# FLOM_Converter.net
KiCad netlist of a schematic drawn in Altium Designer
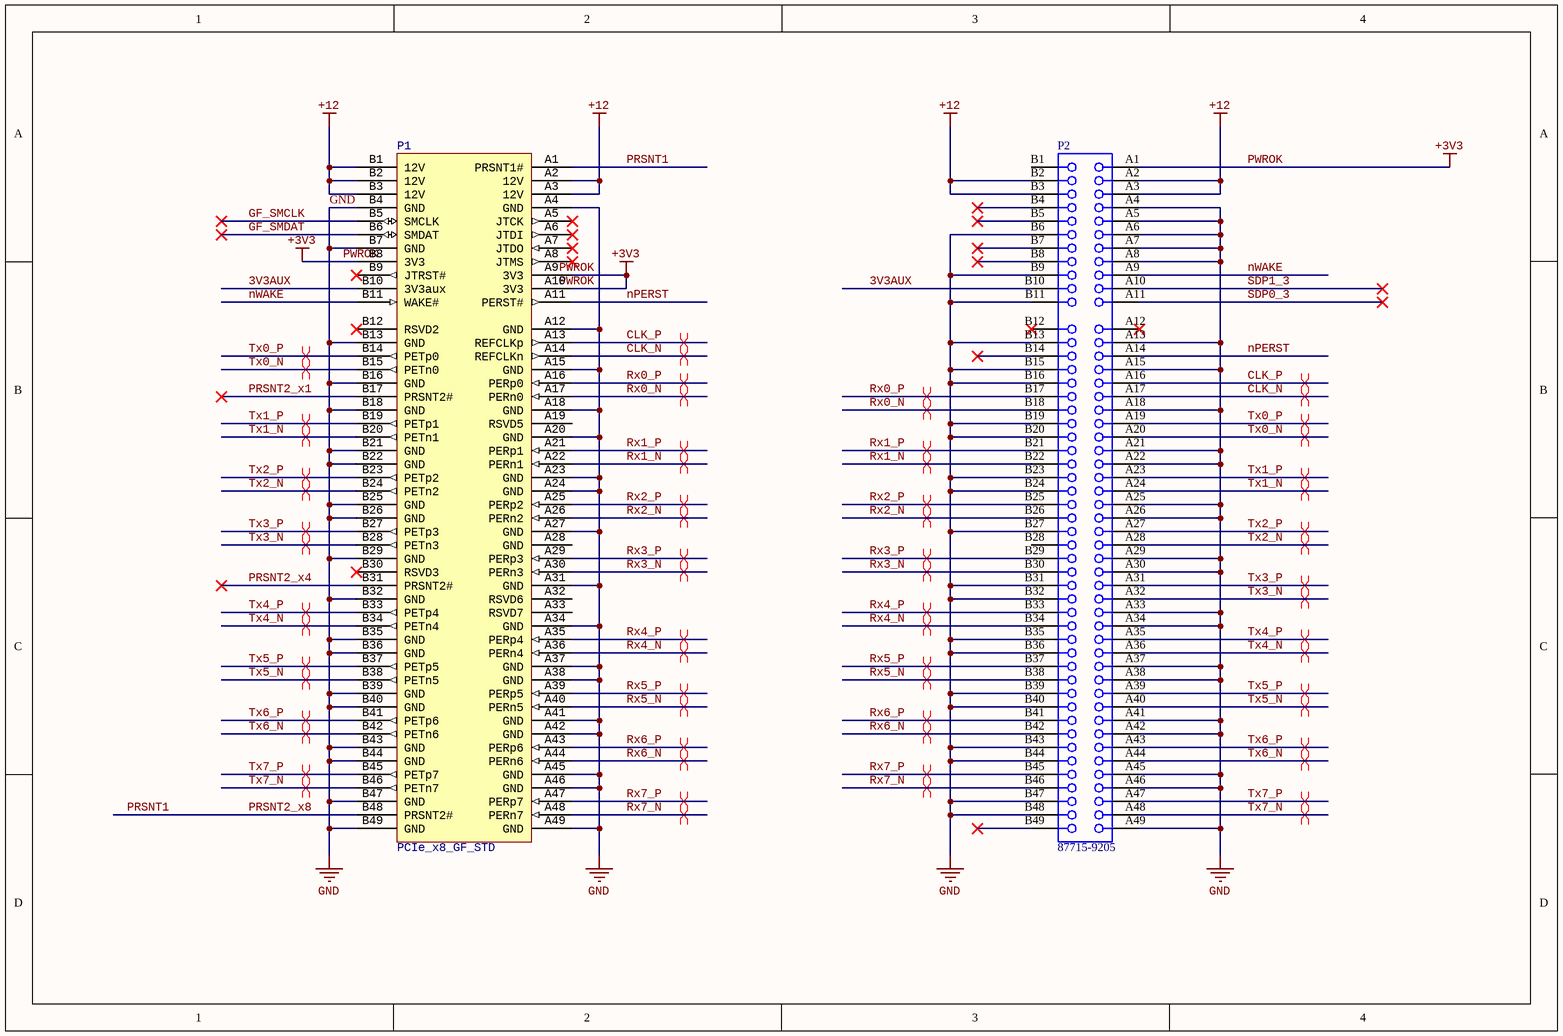
[diagram p0: FLOM_Converter.SchDoc]

(export (version "E")
  (design (tool "Eeschema 10.0.6"))
  (components
    (comp (ref "P1")
      (value "PCIe_x8_GF_STD")
      (footprint "PCIe_x8_GF_STD")
      (libsource (lib "FLOM_Converter") (part "PCIe_x8_GF_STD"))
    )
    (comp (ref "P2")
      (value "87715-9205")
      (footprint "BTB1-00-2V98")
      (description "Board-to-Board Connector, PTH, Vertical, Pitch 1.00mm, 98-Position")
      (fields (field (name "PUBLISHER") "Altium"))
      (libsource (lib "FLOM_Converter") (part "CMP-0001-00128-1"))
    )
  )
  (nets
    (net (code "1") (name "+3V3") (class "Default")
      (node (ref "P1") (pin "A10") (pinfunction "3V3_A10") (pintype "power_in"))
      (node (ref "P1") (pin "A9") (pinfunction "3V3_A9") (pintype "power_in"))
      (node (ref "P1") (pin "B8") (pinfunction "3V3_B8") (pintype "power_in"))
      (node (ref "P2") (pin "A1") (pinfunction "A1_A1") (pintype "passive"))
    )
    (net (code "2") (name "+12") (class "Default")
      (node (ref "P1") (pin "A2") (pinfunction "12V_A2") (pintype "power_in"))
      (node (ref "P1") (pin "A3") (pinfunction "12V_A3") (pintype "power_in"))
      (node (ref "P1") (pin "B1") (pinfunction "12V_B1") (pintype "power_in"))
      (node (ref "P1") (pin "B2") (pinfunction "12V_B2") (pintype "power_in"))
      (node (ref "P1") (pin "B3") (pinfunction "12V_B3") (pintype "power_in"))
      (node (ref "P2") (pin "A2") (pinfunction "A2_A2") (pintype "passive"))
      (node (ref "P2") (pin "A3") (pinfunction "A3_A3") (pintype "passive"))
      (node (ref "P2") (pin "B2") (pinfunction "B2_B2") (pintype "passive"))
      (node (ref "P2") (pin "B3") (pinfunction "B3_B3") (pintype "passive"))
    )
    (net (code "3") (name "/3V3AUX") (class "Default")
      (node (ref "P1") (pin "B10") (pinfunction "3V3aux_B10") (pintype "power_in"))
      (node (ref "P2") (pin "B10") (pinfunction "B10_B10") (pintype "passive"))
    )
    (net (code "5") (name "/CLK_N") (class "Default")
      (node (ref "P1") (pin "A14") (pinfunction "REFCLKn_A14") (pintype "output"))
      (node (ref "P2") (pin "A17") (pinfunction "A17_A17") (pintype "passive"))
    )
    (net (code "6") (name "/CLK_P") (class "Default")
      (node (ref "P1") (pin "A13") (pinfunction "REFCLKp_A13") (pintype "output"))
      (node (ref "P2") (pin "A16") (pinfunction "A16_A16") (pintype "passive"))
    )
    (net (code "7") (name "/GF_SMCLK") (class "Default")
      (node (ref "P1") (pin "B5") (pinfunction "SMCLK_B5") (pintype "bidirectional+no_connect"))
    )
    (net (code "8") (name "/GF_SMDAT") (class "Default")
      (node (ref "P1") (pin "B6") (pinfunction "SMDAT_B6") (pintype "bidirectional+no_connect"))
    )
    (net (code "9") (name "/PRSNT1") (class "Default")
      (node (ref "P1") (pin "A1") (pinfunction "PRSNT1#_A1") (pintype "passive"))
      (node (ref "P1") (pin "B48") (pinfunction "PRSNT2#_B48") (pintype "passive"))
    )
    (net (code "10") (name "/PRSNT2_x1") (class "Default")
      (node (ref "P1") (pin "B17") (pinfunction "PRSNT2#_B17") (pintype "passive+no_connect"))
    )
    (net (code "11") (name "/PRSNT2_x4") (class "Default")
      (node (ref "P1") (pin "B31") (pinfunction "PRSNT2#_B31") (pintype "passive+no_connect"))
    )
    (net (code "12") (name "/Rx0_N") (class "Default")
      (node (ref "P1") (pin "A17") (pinfunction "PERn0_A17") (pintype "input"))
      (node (ref "P2") (pin "B18") (pinfunction "B18_B18") (pintype "passive"))
    )
    (net (code "13") (name "/Rx0_P") (class "Default")
      (node (ref "P1") (pin "A16") (pinfunction "PERp0_A16") (pintype "input"))
      (node (ref "P2") (pin "B17") (pinfunction "B17_B17") (pintype "passive"))
    )
    (net (code "14") (name "/Rx1_N") (class "Default")
      (node (ref "P1") (pin "A22") (pinfunction "PERn1_A22") (pintype "input"))
      (node (ref "P2") (pin "B22") (pinfunction "B22_B22") (pintype "passive"))
    )
    (net (code "15") (name "/Rx1_P") (class "Default")
      (node (ref "P1") (pin "A21") (pinfunction "PERp1_A21") (pintype "input"))
      (node (ref "P2") (pin "B21") (pinfunction "B21_B21") (pintype "passive"))
    )
    (net (code "16") (name "/Rx2_N") (class "Default")
      (node (ref "P1") (pin "A26") (pinfunction "PERn2_A26") (pintype "input"))
      (node (ref "P2") (pin "B26") (pinfunction "B26_B26") (pintype "passive"))
    )
    (net (code "17") (name "/Rx2_P") (class "Default")
      (node (ref "P1") (pin "A25") (pinfunction "PERp2_A25") (pintype "input"))
      (node (ref "P2") (pin "B25") (pinfunction "B25_B25") (pintype "passive"))
    )
    (net (code "18") (name "/Rx3_N") (class "Default")
      (node (ref "P1") (pin "A30") (pinfunction "PERn3_A30") (pintype "input"))
      (node (ref "P2") (pin "B30") (pinfunction "B30_B30") (pintype "passive"))
    )
    (net (code "19") (name "/Rx3_P") (class "Default")
      (node (ref "P1") (pin "A29") (pinfunction "PERp3_A29") (pintype "input"))
      (node (ref "P2") (pin "B29") (pinfunction "B29_B29") (pintype "passive"))
    )
    (net (code "20") (name "/Rx4_N") (class "Default")
      (node (ref "P1") (pin "A36") (pinfunction "PERn4_A36") (pintype "input"))
      (node (ref "P2") (pin "B34") (pinfunction "B34_B34") (pintype "passive"))
    )
    (net (code "21") (name "/Rx4_P") (class "Default")
      (node (ref "P1") (pin "A35") (pinfunction "PERp4_A35") (pintype "input"))
      (node (ref "P2") (pin "B33") (pinfunction "B33_B33") (pintype "passive"))
    )
    (net (code "22") (name "/Rx5_N") (class "Default")
      (node (ref "P1") (pin "A40") (pinfunction "PERn5_A40") (pintype "input"))
      (node (ref "P2") (pin "B38") (pinfunction "B38_B38") (pintype "passive"))
    )
    (net (code "23") (name "/Rx5_P") (class "Default")
      (node (ref "P1") (pin "A39") (pinfunction "PERp5_A39") (pintype "input"))
      (node (ref "P2") (pin "B37") (pinfunction "B37_B37") (pintype "passive"))
    )
    (net (code "24") (name "/Rx6_N") (class "Default")
      (node (ref "P1") (pin "A44") (pinfunction "PERn6_A44") (pintype "input"))
      (node (ref "P2") (pin "B42") (pinfunction "B42_B42") (pintype "passive"))
    )
    (net (code "25") (name "/Rx6_P") (class "Default")
      (node (ref "P1") (pin "A43") (pinfunction "PERp6_A43") (pintype "input"))
      (node (ref "P2") (pin "B41") (pinfunction "B41_B41") (pintype "passive"))
    )
    (net (code "26") (name "/Rx7_N") (class "Default")
      (node (ref "P1") (pin "A48") (pinfunction "PERn7_A48") (pintype "input"))
      (node (ref "P2") (pin "B46") (pinfunction "B46_B46") (pintype "passive"))
    )
    (net (code "27") (name "/Rx7_P") (class "Default")
      (node (ref "P1") (pin "A47") (pinfunction "PERp7_A47") (pintype "input"))
      (node (ref "P2") (pin "B45") (pinfunction "B45_B45") (pintype "passive"))
    )
    (net (code "28") (name "/SDP0_3") (class "Default")
      (node (ref "P2") (pin "A11") (pinfunction "A11_A11") (pintype "passive+no_connect"))
    )
    (net (code "29") (name "/SDP1_3") (class "Default")
      (node (ref "P2") (pin "A10") (pinfunction "A10_A10") (pintype "passive+no_connect"))
    )
    (net (code "30") (name "/Tx0_N") (class "Default")
      (node (ref "P1") (pin "B15") (pinfunction "PETn0_B15") (pintype "output"))
      (node (ref "P2") (pin "A20") (pinfunction "A20_A20") (pintype "passive"))
    )
    (net (code "31") (name "/Tx0_P") (class "Default")
      (node (ref "P1") (pin "B14") (pinfunction "PETp0_B14") (pintype "output"))
      (node (ref "P2") (pin "A19") (pinfunction "A19_A19") (pintype "passive"))
    )
    (net (code "32") (name "/Tx1_N") (class "Default")
      (node (ref "P1") (pin "B20") (pinfunction "PETn1_B20") (pintype "output"))
      (node (ref "P2") (pin "A24") (pinfunction "A24_A24") (pintype "passive"))
    )
    (net (code "33") (name "/Tx1_P") (class "Default")
      (node (ref "P1") (pin "B19") (pinfunction "PETp1_B19") (pintype "output"))
      (node (ref "P2") (pin "A23") (pinfunction "A23_A23") (pintype "passive"))
    )
    (net (code "34") (name "/Tx2_N") (class "Default")
      (node (ref "P1") (pin "B24") (pinfunction "PETn2_B24") (pintype "output"))
      (node (ref "P2") (pin "A28") (pinfunction "A28_A28") (pintype "passive"))
    )
    (net (code "35") (name "/Tx2_P") (class "Default")
      (node (ref "P1") (pin "B23") (pinfunction "PETp2_B23") (pintype "output"))
      (node (ref "P2") (pin "A27") (pinfunction "A27_A27") (pintype "passive"))
    )
    (net (code "36") (name "/Tx3_N") (class "Default")
      (node (ref "P1") (pin "B28") (pinfunction "PETn3_B28") (pintype "output"))
      (node (ref "P2") (pin "A32") (pinfunction "A32_A32") (pintype "passive"))
    )
    (net (code "37") (name "/Tx3_P") (class "Default")
      (node (ref "P1") (pin "B27") (pinfunction "PETp3_B27") (pintype "output"))
      (node (ref "P2") (pin "A31") (pinfunction "A31_A31") (pintype "passive"))
    )
    (net (code "38") (name "/Tx4_N") (class "Default")
      (node (ref "P1") (pin "B34") (pinfunction "PETn4_B34") (pintype "output"))
      (node (ref "P2") (pin "A36") (pinfunction "A36_A36") (pintype "passive"))
    )
    (net (code "39") (name "/Tx4_P") (class "Default")
      (node (ref "P1") (pin "B33") (pinfunction "PETp4_B33") (pintype "output"))
      (node (ref "P2") (pin "A35") (pinfunction "A35_A35") (pintype "passive"))
    )
    (net (code "40") (name "/Tx5_N") (class "Default")
      (node (ref "P1") (pin "B38") (pinfunction "PETn5_B38") (pintype "output"))
      (node (ref "P2") (pin "A40") (pinfunction "A40_A40") (pintype "passive"))
    )
    (net (code "41") (name "/Tx5_P") (class "Default")
      (node (ref "P1") (pin "B37") (pinfunction "PETp5_B37") (pintype "output"))
      (node (ref "P2") (pin "A39") (pinfunction "A39_A39") (pintype "passive"))
    )
    (net (code "42") (name "/Tx6_N") (class "Default")
      (node (ref "P1") (pin "B42") (pinfunction "PETn6_B42") (pintype "output"))
      (node (ref "P2") (pin "A44") (pinfunction "A44_A44") (pintype "passive"))
    )
    (net (code "43") (name "/Tx6_P") (class "Default")
      (node (ref "P1") (pin "B41") (pinfunction "PETp6_B41") (pintype "output"))
      (node (ref "P2") (pin "A43") (pinfunction "A43_A43") (pintype "passive"))
    )
    (net (code "44") (name "/Tx7_N") (class "Default")
      (node (ref "P1") (pin "B46") (pinfunction "PETn7_B46") (pintype "output"))
      (node (ref "P2") (pin "A48") (pinfunction "A48_A48") (pintype "passive"))
    )
    (net (code "45") (name "/Tx7_P") (class "Default")
      (node (ref "P1") (pin "B45") (pinfunction "PETp7_B45") (pintype "output"))
      (node (ref "P2") (pin "A47") (pinfunction "A47_A47") (pintype "passive"))
    )
    (net (code "46") (name "/nPERST") (class "Default")
      (node (ref "P1") (pin "A11") (pinfunction "PERST#_A11") (pintype "output"))
      (node (ref "P2") (pin "A14") (pinfunction "A14_A14") (pintype "passive"))
    )
    (net (code "47") (name "/nWAKE") (class "Default")
      (node (ref "P1") (pin "B11") (pinfunction "WAKE#_B11") (pintype "input"))
      (node (ref "P2") (pin "A9") (pinfunction "A9_A9") (pintype "passive"))
    )
    (net (code "48") (name "GND") (class "Default")
      (node (ref "P1") (pin "A12") (pinfunction "GND_A12") (pintype "power_in"))
      (node (ref "P1") (pin "A15") (pinfunction "GND_A15") (pintype "power_in"))
      (node (ref "P1") (pin "A18") (pinfunction "GND_A18") (pintype "power_in"))
      (node (ref "P1") (pin "A20") (pinfunction "GND_A20") (pintype "power_in"))
      (node (ref "P1") (pin "A23") (pinfunction "GND_A23") (pintype "power_in"))
      (node (ref "P1") (pin "A24") (pinfunction "GND_A24") (pintype "power_in"))
      (node (ref "P1") (pin "A27") (pinfunction "GND_A27") (pintype "power_in"))
      (node (ref "P1") (pin "A31") (pinfunction "GND_A31") (pintype "power_in"))
      (node (ref "P1") (pin "A34") (pinfunction "GND_A34") (pintype "power_in"))
      (node (ref "P1") (pin "A37") (pinfunction "GND_A37") (pintype "power_in"))
      (node (ref "P1") (pin "A38") (pinfunction "GND_A38") (pintype "power_in"))
      (node (ref "P1") (pin "A4") (pinfunction "GND_A4") (pintype "power_in"))
      (node (ref "P1") (pin "A41") (pinfunction "GND_A41") (pintype "power_in"))
      (node (ref "P1") (pin "A42") (pinfunction "GND_A42") (pintype "power_in"))
      (node (ref "P1") (pin "A45") (pinfunction "GND_A45") (pintype "power_in"))
      (node (ref "P1") (pin "A46") (pinfunction "GND_A46") (pintype "power_in"))
      (node (ref "P1") (pin "A49") (pinfunction "GND_A49") (pintype "power_in"))
      (node (ref "P1") (pin "B13") (pinfunction "GND_B13") (pintype "power_in"))
      (node (ref "P1") (pin "B16") (pinfunction "GND_B16") (pintype "power_in"))
      (node (ref "P1") (pin "B18") (pinfunction "GND_B18") (pintype "power_in"))
      (node (ref "P1") (pin "B21") (pinfunction "GND_B21") (pintype "power_in"))
      (node (ref "P1") (pin "B22") (pinfunction "GND_B22") (pintype "power_in"))
      (node (ref "P1") (pin "B25") (pinfunction "GND_B25") (pintype "power_in"))
      (node (ref "P1") (pin "B26") (pinfunction "GND_B26") (pintype "power_in"))
      (node (ref "P1") (pin "B29") (pinfunction "GND_B29") (pintype "power_in"))
      (node (ref "P1") (pin "B32") (pinfunction "GND_B32") (pintype "power_in"))
      (node (ref "P1") (pin "B35") (pinfunction "GND_B35") (pintype "power_in"))
      (node (ref "P1") (pin "B36") (pinfunction "GND_B36") (pintype "power_in"))
      (node (ref "P1") (pin "B39") (pinfunction "GND_B39") (pintype "power_in"))
      (node (ref "P1") (pin "B4") (pinfunction "GND_B4") (pintype "power_in"))
      (node (ref "P1") (pin "B40") (pinfunction "GND_B40") (pintype "power_in"))
      (node (ref "P1") (pin "B43") (pinfunction "GND_B43") (pintype "power_in"))
      (node (ref "P1") (pin "B44") (pinfunction "GND_B44") (pintype "power_in"))
      (node (ref "P1") (pin "B47") (pinfunction "GND_B47") (pintype "power_in"))
      (node (ref "P1") (pin "B49") (pinfunction "GND_B49") (pintype "power_in"))
      (node (ref "P1") (pin "B7") (pinfunction "GND_B7") (pintype "power_in"))
      (node (ref "P2") (pin "A13") (pinfunction "A13_A13") (pintype "passive"))
      (node (ref "P2") (pin "A15") (pinfunction "A15_A15") (pintype "passive"))
      (node (ref "P2") (pin "A18") (pinfunction "A18_A18") (pintype "passive"))
      (node (ref "P2") (pin "A21") (pinfunction "A21_A21") (pintype "passive"))
      (node (ref "P2") (pin "A22") (pinfunction "A22_A22") (pintype "passive"))
      (node (ref "P2") (pin "A25") (pinfunction "A25_A25") (pintype "passive"))
      (node (ref "P2") (pin "A26") (pinfunction "A26_A26") (pintype "passive"))
      (node (ref "P2") (pin "A29") (pinfunction "A29_A29") (pintype "passive"))
      (node (ref "P2") (pin "A30") (pinfunction "A30_A30") (pintype "passive"))
      (node (ref "P2") (pin "A33") (pinfunction "A33_A33") (pintype "passive"))
      (node (ref "P2") (pin "A34") (pinfunction "A34_A34") (pintype "passive"))
      (node (ref "P2") (pin "A37") (pinfunction "A37_A37") (pintype "passive"))
      (node (ref "P2") (pin "A38") (pinfunction "A38_A38") (pintype "passive"))
      (node (ref "P2") (pin "A4") (pinfunction "A4_A4") (pintype "passive"))
      (node (ref "P2") (pin "A41") (pinfunction "A41_A41") (pintype "passive"))
      (node (ref "P2") (pin "A42") (pinfunction "A42_A42") (pintype "passive"))
      (node (ref "P2") (pin "A45") (pinfunction "A45_A45") (pintype "passive"))
      (node (ref "P2") (pin "A46") (pinfunction "A46_A46") (pintype "passive"))
      (node (ref "P2") (pin "A49") (pinfunction "A49_A49") (pintype "passive"))
      (node (ref "P2") (pin "A5") (pinfunction "A5_A5") (pintype "passive"))
      (node (ref "P2") (pin "A6") (pinfunction "A6_A6") (pintype "passive"))
      (node (ref "P2") (pin "A7") (pinfunction "A7_A7") (pintype "passive"))
      (node (ref "P2") (pin "A8") (pinfunction "A8_A8") (pintype "passive"))
      (node (ref "P2") (pin "B11") (pinfunction "B11_B11") (pintype "passive"))
      (node (ref "P2") (pin "B13") (pinfunction "B13_B13") (pintype "passive"))
      (node (ref "P2") (pin "B15") (pinfunction "B15_B15") (pintype "passive"))
      (node (ref "P2") (pin "B16") (pinfunction "B16_B16") (pintype "passive"))
      (node (ref "P2") (pin "B19") (pinfunction "B19_B19") (pintype "passive"))
      (node (ref "P2") (pin "B20") (pinfunction "B20_B20") (pintype "passive"))
      (node (ref "P2") (pin "B23") (pinfunction "B23_B23") (pintype "passive"))
      (node (ref "P2") (pin "B24") (pinfunction "B24_B24") (pintype "passive"))
      (node (ref "P2") (pin "B27") (pinfunction "B27_B27") (pintype "passive"))
      (node (ref "P2") (pin "B31") (pinfunction "B31_B31") (pintype "passive"))
      (node (ref "P2") (pin "B32") (pinfunction "B32_B32") (pintype "passive"))
      (node (ref "P2") (pin "B35") (pinfunction "B35_B35") (pintype "passive"))
      (node (ref "P2") (pin "B36") (pinfunction "B36_B36") (pintype "passive"))
      (node (ref "P2") (pin "B39") (pinfunction "B39_B39") (pintype "passive"))
      (node (ref "P2") (pin "B40") (pinfunction "B40_B40") (pintype "passive"))
      (node (ref "P2") (pin "B43") (pinfunction "B43_B43") (pintype "passive"))
      (node (ref "P2") (pin "B44") (pinfunction "B44_B44") (pintype "passive"))
      (node (ref "P2") (pin "B47") (pinfunction "B47_B47") (pintype "passive"))
      (node (ref "P2") (pin "B48") (pinfunction "B48_B48") (pintype "passive"))
      (node (ref "P2") (pin "B6") (pinfunction "B6_B6") (pintype "passive"))
      (node (ref "P2") (pin "B9") (pinfunction "B9_B9") (pintype "passive"))
    )
    (net (code "49") (name "unconnected-(P1-GND-PadA28)") (class "Default")
      (node (ref "P1") (pin "A28") (pinfunction "GND_A28") (pintype "power_in"))
    )
    (net (code "50") (name "unconnected-(P1-JTCK-PadA5)") (class "Default")
      (node (ref "P1") (pin "A5") (pinfunction "JTCK_A5") (pintype "output+no_connect"))
    )
    (net (code "51") (name "unconnected-(P1-JTDI-PadA6)") (class "Default")
      (node (ref "P1") (pin "A6") (pinfunction "JTDI_A6") (pintype "output+no_connect"))
    )
    (net (code "52") (name "unconnected-(P1-JTDO-PadA7)") (class "Default")
      (node (ref "P1") (pin "A7") (pinfunction "JTDO_A7") (pintype "input+no_connect"))
    )
    (net (code "53") (name "unconnected-(P1-JTMS-PadA8)") (class "Default")
      (node (ref "P1") (pin "A8") (pinfunction "JTMS_A8") (pintype "output+no_connect"))
    )
    (net (code "54") (name "unconnected-(P1-JTRST#-PadB9)") (class "Default")
      (node (ref "P1") (pin "B9") (pinfunction "JTRST#_B9") (pintype "output+no_connect"))
    )
    (net (code "55") (name "unconnected-(P1-RSVD2-PadB12)") (class "Default")
      (node (ref "P1") (pin "B12") (pinfunction "RSVD2_B12") (pintype "passive+no_connect"))
    )
    (net (code "56") (name "unconnected-(P1-RSVD3-PadB30)") (class "Default")
      (node (ref "P1") (pin "B30") (pinfunction "RSVD3_B30") (pintype "passive+no_connect"))
    )
    (net (code "57") (name "unconnected-(P1-RSVD5-PadA19)") (class "Default")
      (node (ref "P1") (pin "A19") (pinfunction "RSVD5_A19") (pintype "passive"))
    )
    (net (code "58") (name "unconnected-(P1-RSVD6-PadA32)") (class "Default")
      (node (ref "P1") (pin "A32") (pinfunction "RSVD6_A32") (pintype "passive"))
    )
    (net (code "59") (name "unconnected-(P1-RSVD7-PadA33)") (class "Default")
      (node (ref "P1") (pin "A33") (pinfunction "RSVD7_A33") (pintype "passive"))
    )
    (net (code "60") (name "unconnected-(P2-PadA12)") (class "Default")
      (node (ref "P2") (pin "A12") (pinfunction "A12_A12") (pintype "passive+no_connect"))
    )
    (net (code "61") (name "unconnected-(P2-PadB1)") (class "Default")
      (node (ref "P2") (pin "B1") (pinfunction "B1_B1") (pintype "passive"))
    )
    (net (code "62") (name "unconnected-(P2-PadB4)") (class "Default")
      (node (ref "P2") (pin "B4") (pinfunction "B4_B4") (pintype "passive+no_connect"))
    )
    (net (code "63") (name "unconnected-(P2-PadB5)") (class "Default")
      (node (ref "P2") (pin "B5") (pinfunction "B5_B5") (pintype "passive+no_connect"))
    )
    (net (code "64") (name "unconnected-(P2-PadB7)") (class "Default")
      (node (ref "P2") (pin "B7") (pinfunction "B7_B7") (pintype "passive+no_connect"))
    )
    (net (code "65") (name "unconnected-(P2-PadB8)") (class "Default")
      (node (ref "P2") (pin "B8") (pinfunction "B8_B8") (pintype "passive+no_connect"))
    )
    (net (code "66") (name "unconnected-(P2-PadB12)") (class "Default")
      (node (ref "P2") (pin "B12") (pinfunction "B12_B12") (pintype "passive+no_connect"))
    )
    (net (code "67") (name "unconnected-(P2-PadB14)") (class "Default")
      (node (ref "P2") (pin "B14") (pinfunction "B14_B14") (pintype "passive+no_connect"))
    )
    (net (code "68") (name "unconnected-(P2-PadB28)") (class "Default")
      (node (ref "P2") (pin "B28") (pinfunction "B28_B28") (pintype "passive"))
    )
    (net (code "69") (name "unconnected-(P2-PadB49)") (class "Default")
      (node (ref "P2") (pin "B49") (pinfunction "B49_B49") (pintype "passive+no_connect"))
    )
  )
)
